# Yitran_IT900_Hutschiene_1_0.net
KiCad netlist of a schematic drawn in EAGLE
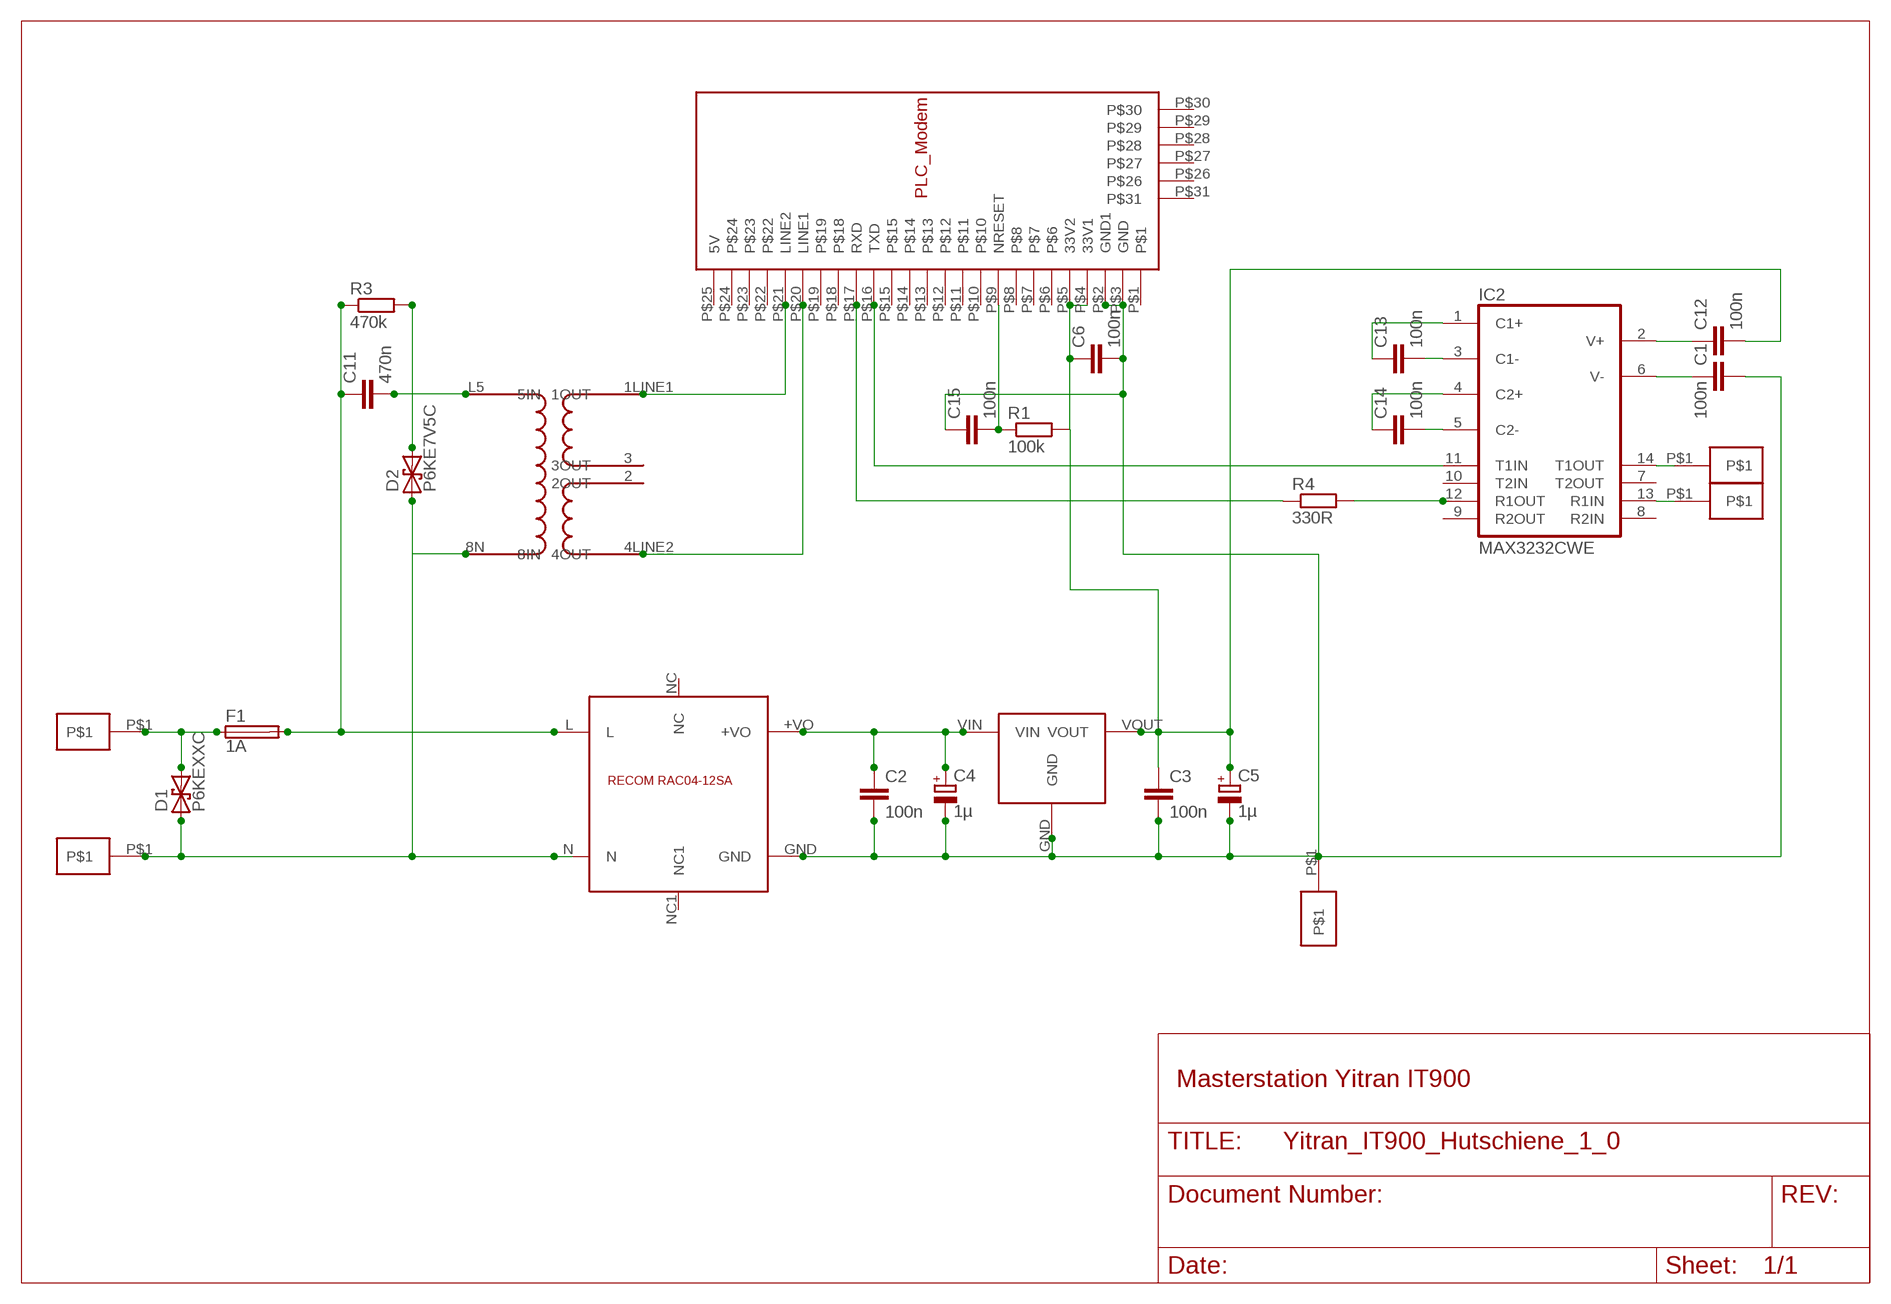
[diagram p0: schematic, sheet 1]

(export (version "E")
  (design (tool "Eeschema 10.0.6"))
  (components
    (comp (ref "C1")
      (value "100n")
      (footprint "eagle-import:C1206K")
      (libsource (lib "eagle-import") (part "C-EUC1206K"))
    )
    (comp (ref "C2")
      (value "100n")
      (footprint "eagle-import:C1206K")
      (libsource (lib "eagle-import") (part "C-EUC1206K"))
    )
    (comp (ref "C3")
      (value "100n")
      (footprint "eagle-import:C1206K")
      (libsource (lib "eagle-import") (part "C-EUC1206K"))
    )
    (comp (ref "C4")
      (value "1µ")
      (footprint "eagle-import:E2,5-5")
      (libsource (lib "eagle-import") (part "CPOL-EUE2.5-5"))
    )
    (comp (ref "C5")
      (value "1µ")
      (footprint "eagle-import:E2,5-5")
      (libsource (lib "eagle-import") (part "CPOL-EUE2.5-5"))
    )
    (comp (ref "C6")
      (value "100n")
      (footprint "eagle-import:C1206K")
      (libsource (lib "eagle-import") (part "C-EUC1206K"))
    )
    (comp (ref "C11")
      (value "470n")
      (footprint "eagle-import:C150-091X182")
      (libsource (lib "eagle-import") (part "C-EU150-091X182"))
    )
    (comp (ref "C12")
      (value "100n")
      (footprint "eagle-import:C1206K")
      (libsource (lib "eagle-import") (part "C-EUC1206K"))
    )
    (comp (ref "C13")
      (value "100n")
      (footprint "eagle-import:C1206K")
      (libsource (lib "eagle-import") (part "C-EUC1206K"))
    )
    (comp (ref "C14")
      (value "100n")
      (footprint "eagle-import:C1206K")
      (libsource (lib "eagle-import") (part "C-EUC1206K"))
    )
    (comp (ref "C15")
      (value "100n")
      (footprint "eagle-import:C1206K")
      (libsource (lib "eagle-import") (part "C-EUC1206K"))
    )
    (comp (ref "D1")
      (value "P6KEXXC")
      (footprint "eagle-import:CB417-15")
      (libsource (lib "eagle-import") (part "P6KEXXC"))
    )
    (comp (ref "D2")
      (value "P6KE7V5C")
      (footprint "eagle-import:CB417-15")
      (libsource (lib "eagle-import") (part "P6KEXXC"))
    )
    (comp (ref "F1")
      (value "1A")
      (footprint "eagle-import:TR5")
      (libsource (lib "eagle-import") (part "TR5"))
    )
    (comp (ref "GND")
      (value "PN4")
      (footprint "eagle-import:PIN2")
      (libsource (lib "eagle-import") (part "PN4"))
    )
    (comp (ref "IC2")
      (value "MAX3232CWE")
      (footprint "eagle-import:SO16L")
      (fields (field (name "MF") "MAXIM") (field (name "MPN") "MAX3232CWE+"))
      (libsource (lib "eagle-import") (part "MAX3232WEC"))
    )
    (comp (ref "PL1")
      (value "PN4")
      (footprint "eagle-import:PIN2")
      (libsource (lib "eagle-import") (part "PN4"))
    )
    (comp (ref "PL2")
      (value "PN4")
      (footprint "eagle-import:PIN2")
      (libsource (lib "eagle-import") (part "PN4"))
    )
    (comp (ref "R1")
      (value "100k")
      (footprint "eagle-import:M1406")
      (libsource (lib "eagle-import") (part "R-EU_M1406"))
    )
    (comp (ref "R3")
      (value "470k")
      (footprint "eagle-import:0309_10")
      (libsource (lib "eagle-import") (part "R-EU_0309/10"))
    )
    (comp (ref "R4")
      (value "330R")
      (footprint "eagle-import:R1206")
      (libsource (lib "eagle-import") (part "R-EU_R1206"))
    )
    (comp (ref "RXD")
      (value "PN4")
      (footprint "eagle-import:PIN2")
      (libsource (lib "eagle-import") (part "PN4"))
    )
    (comp (ref "TXD")
      (value "PN4")
      (footprint "eagle-import:PIN2")
      (libsource (lib "eagle-import") (part "PN4"))
    )
    (comp (ref "U$1")
      (value "RECOM_783_3")
      (footprint "eagle-import:RECOM785X")
      (libsource (lib "eagle-import") (part "RECOM_785_05"))
    )
    (comp (ref "U$3")
      (value "MODEMSTECKER")
      (footprint "eagle-import:MODEM_FUSS")
      (libsource (lib "eagle-import") (part "MODEMSTECKER"))
    )
    (comp (ref "U$9")
      (value "RECOM_RAC04_12SA")
      (footprint "eagle-import:RAC04_12SA")
      (libsource (lib "eagle-import") (part "RECOM_RAC04_12SA"))
    )
    (comp (ref "U$10")
      (value "PLC_UEBERTRAGER_V2")
      (footprint "eagle-import:PLC-UEBERTRAGER_V2")
      (libsource (lib "eagle-import") (part "PLC_UEBERTRAGER_V2"))
    )
  )
  (nets
    (net (code "1") (name "Net-(C2-Pad1)") (class "Default")
      (node (ref "C2") (pin "1") (pinfunction "1_1") (pintype "passive"))
      (node (ref "C4") (pin "+") (pinfunction "+_+") (pintype "passive"))
      (node (ref "U$1") (pin "VIN") (pinfunction "VIN_VIN") (pintype "bidirectional"))
      (node (ref "U$9") (pin "+VO") (pinfunction "+VO_+VO") (pintype "bidirectional"))
    )
    (net (code "2") (name "Net-(C11-Pad1)") (class "Default")
      (node (ref "C11") (pin "1") (pinfunction "1_1") (pintype "passive"))
      (node (ref "F1") (pin "2") (pinfunction "2_2") (pintype "passive"))
      (node (ref "R3") (pin "1") (pinfunction "1_1") (pintype "passive"))
      (node (ref "U$9") (pin "L") (pinfunction "L_L") (pintype "bidirectional"))
    )
    (net (code "3") (name "Net-(D1-1)") (class "Default")
      (node (ref "D1") (pin "A") (pinfunction "1_A") (pintype "passive"))
      (node (ref "D2") (pin "A") (pinfunction "1_A") (pintype "passive"))
      (node (ref "PL2") (pin "P$1") (pinfunction "P$1_P$1") (pintype "bidirectional"))
      (node (ref "U$10") (pin "8N") (pinfunction "8IN_8N") (pintype "input"))
      (node (ref "U$9") (pin "N") (pinfunction "N_N") (pintype "bidirectional"))
    )
    (net (code "4") (name "Net-(D1-2)") (class "Default")
      (node (ref "D1") (pin "C") (pinfunction "2_C") (pintype "passive"))
      (node (ref "F1") (pin "1") (pinfunction "1_1") (pintype "passive"))
      (node (ref "PL1") (pin "P$1") (pinfunction "P$1_P$1") (pintype "bidirectional"))
    )
    (net (code "5") (name "Net-(D2-2)") (class "Default")
      (node (ref "C11") (pin "2") (pinfunction "2_2") (pintype "passive"))
      (node (ref "D2") (pin "C") (pinfunction "2_C") (pintype "passive"))
      (node (ref "R3") (pin "2") (pinfunction "2_2") (pintype "passive"))
      (node (ref "U$10") (pin "L5") (pinfunction "5IN_L5") (pintype "input"))
    )
    (net (code "6") (name "Net-(IC2A-C1+)") (class "Default")
      (node (ref "C13") (pin "1") (pinfunction "1_1") (pintype "passive"))
      (node (ref "IC2") (pin "1") (pinfunction "C1+_1") (pintype "bidirectional"))
    )
    (net (code "7") (name "Net-(IC2A-C1-)") (class "Default")
      (node (ref "C13") (pin "2") (pinfunction "2_2") (pintype "passive"))
      (node (ref "IC2") (pin "3") (pinfunction "C1-_3") (pintype "bidirectional"))
    )
    (net (code "8") (name "Net-(IC2A-C2+)") (class "Default")
      (node (ref "C14") (pin "1") (pinfunction "1_1") (pintype "passive"))
      (node (ref "IC2") (pin "4") (pinfunction "C2+_4") (pintype "bidirectional"))
    )
    (net (code "9") (name "Net-(IC2A-C2-)") (class "Default")
      (node (ref "C14") (pin "2") (pinfunction "2_2") (pintype "passive"))
      (node (ref "IC2") (pin "5") (pinfunction "C2-_5") (pintype "bidirectional"))
    )
    (net (code "10") (name "Net-(IC2A-R1IN)") (class "Default")
      (node (ref "IC2") (pin "13") (pinfunction "R1IN_13") (pintype "input"))
      (node (ref "RXD") (pin "P$1") (pinfunction "P$1_P$1") (pintype "bidirectional"))
    )
    (net (code "11") (name "Net-(IC2A-R1OUT)") (class "Default")
      (node (ref "IC2") (pin "12") (pinfunction "R1OUT_12") (pintype "output"))
      (node (ref "R4") (pin "2") (pinfunction "2_2") (pintype "passive"))
    )
    (net (code "12") (name "Net-(IC2A-T1IN)") (class "Default")
      (node (ref "IC2") (pin "11") (pinfunction "T1IN_11") (pintype "input"))
      (node (ref "U$3") (pin "P$16") (pinfunction "TXD_P$16") (pintype "bidirectional"))
    )
    (net (code "13") (name "Net-(IC2A-T1OUT)") (class "Default")
      (node (ref "IC2") (pin "14") (pinfunction "T1OUT_14") (pintype "output"))
      (node (ref "TXD") (pin "P$1") (pinfunction "P$1_P$1") (pintype "bidirectional"))
    )
    (net (code "14") (name "Net-(IC2A-V+)") (class "Default")
      (node (ref "C12") (pin "1") (pinfunction "1_1") (pintype "passive"))
      (node (ref "IC2") (pin "2") (pinfunction "V+_2") (pintype "bidirectional"))
    )
    (net (code "15") (name "Net-(IC2A-V-)") (class "Default")
      (node (ref "C1") (pin "1") (pinfunction "1_1") (pintype "passive"))
      (node (ref "IC2") (pin "6") (pinfunction "V-_6") (pintype "bidirectional"))
    )
    (net (code "16") (name "Net-(U$3-33V1)") (class "Default")
      (node (ref "C12") (pin "2") (pinfunction "2_2") (pintype "passive"))
      (node (ref "C3") (pin "1") (pinfunction "1_1") (pintype "passive"))
      (node (ref "C5") (pin "+") (pinfunction "+_+") (pintype "passive"))
      (node (ref "C6") (pin "1") (pinfunction "1_1") (pintype "passive"))
      (node (ref "R1") (pin "2") (pinfunction "2_2") (pintype "passive"))
      (node (ref "U$1") (pin "VOUT") (pinfunction "VOUT_VOUT") (pintype "bidirectional"))
      (node (ref "U$3") (pin "P$4") (pinfunction "33V1_P$4") (pintype "bidirectional"))
      (node (ref "U$3") (pin "P$5") (pinfunction "33V2_P$5") (pintype "bidirectional"))
    )
    (net (code "17") (name "Net-(U$3-GND)") (class "Default")
      (node (ref "C1") (pin "2") (pinfunction "2_2") (pintype "passive"))
      (node (ref "C15") (pin "1") (pinfunction "1_1") (pintype "passive"))
      (node (ref "C2") (pin "2") (pinfunction "2_2") (pintype "passive"))
      (node (ref "C3") (pin "2") (pinfunction "2_2") (pintype "passive"))
      (node (ref "C4") (pin "-") (pinfunction "-_-") (pintype "passive"))
      (node (ref "C5") (pin "-") (pinfunction "-_-") (pintype "passive"))
      (node (ref "C6") (pin "2") (pinfunction "2_2") (pintype "passive"))
      (node (ref "GND") (pin "P$1") (pinfunction "P$1_P$1") (pintype "bidirectional"))
      (node (ref "U$1") (pin "GND") (pinfunction "GND_GND") (pintype "bidirectional"))
      (node (ref "U$3") (pin "P$2") (pinfunction "GND1_P$2") (pintype "bidirectional"))
      (node (ref "U$3") (pin "P$3") (pinfunction "GND_P$3") (pintype "bidirectional"))
      (node (ref "U$9") (pin "GND") (pinfunction "GND_GND") (pintype "bidirectional"))
    )
    (net (code "18") (name "Net-(U$3-NRESET)") (class "Default")
      (node (ref "C15") (pin "2") (pinfunction "2_2") (pintype "passive"))
      (node (ref "R1") (pin "1") (pinfunction "1_1") (pintype "passive"))
      (node (ref "U$3") (pin "P$9") (pinfunction "NRESET_P$9") (pintype "bidirectional"))
    )
    (net (code "19") (name "Net-(U$3-RXD)") (class "Default")
      (node (ref "R4") (pin "1") (pinfunction "1_1") (pintype "passive"))
      (node (ref "U$3") (pin "P$17") (pinfunction "RXD_P$17") (pintype "bidirectional"))
    )
    (net (code "20") (name "Net-(U$10-1OUT)") (class "Default")
      (node (ref "U$10") (pin "1LINE1") (pinfunction "1OUT_1LINE1") (pintype "output"))
      (node (ref "U$3") (pin "P$21") (pinfunction "LINE2_P$21") (pintype "bidirectional"))
    )
    (net (code "21") (name "Net-(U$10-4OUT)") (class "Default")
      (node (ref "U$10") (pin "4LINE2") (pinfunction "4OUT_4LINE2") (pintype "output"))
      (node (ref "U$3") (pin "P$20") (pinfunction "LINE1_P$20") (pintype "bidirectional"))
    )
    (net (code "22") (name "unconnected-(IC2A-R2IN-Pad8)") (class "Default")
      (node (ref "IC2") (pin "8") (pinfunction "R2IN_8") (pintype "input"))
    )
    (net (code "23") (name "unconnected-(IC2A-R2OUT-Pad9)") (class "Default")
      (node (ref "IC2") (pin "9") (pinfunction "R2OUT_9") (pintype "output"))
    )
    (net (code "24") (name "unconnected-(IC2A-T2IN-Pad10)") (class "Default")
      (node (ref "IC2") (pin "10") (pinfunction "T2IN_10") (pintype "input"))
    )
    (net (code "25") (name "unconnected-(IC2A-T2OUT-Pad7)") (class "Default")
      (node (ref "IC2") (pin "7") (pinfunction "T2OUT_7") (pintype "output"))
    )
    (net (code "26") (name "unconnected-(U$3-5V-PadP$25)") (class "Default")
      (node (ref "U$3") (pin "P$25") (pinfunction "5V_P$25") (pintype "bidirectional"))
    )
    (net (code "27") (name "unconnected-(U$3-PadP$1)") (class "Default")
      (node (ref "U$3") (pin "P$1") (pinfunction "P$1_P$1") (pintype "bidirectional"))
    )
    (net (code "28") (name "unconnected-(U$3-PadP$6)") (class "Default")
      (node (ref "U$3") (pin "P$6") (pinfunction "P$6_P$6") (pintype "bidirectional"))
    )
    (net (code "29") (name "unconnected-(U$3-PadP$7)") (class "Default")
      (node (ref "U$3") (pin "P$7") (pinfunction "P$7_P$7") (pintype "bidirectional"))
    )
    (net (code "30") (name "unconnected-(U$3-PadP$8)") (class "Default")
      (node (ref "U$3") (pin "P$8") (pinfunction "P$8_P$8") (pintype "bidirectional"))
    )
    (net (code "31") (name "unconnected-(U$3-PadP$10)") (class "Default")
      (node (ref "U$3") (pin "P$10") (pinfunction "P$10_P$10") (pintype "bidirectional"))
    )
    (net (code "32") (name "unconnected-(U$3-PadP$11)") (class "Default")
      (node (ref "U$3") (pin "P$11") (pinfunction "P$11_P$11") (pintype "bidirectional"))
    )
    (net (code "33") (name "unconnected-(U$3-PadP$12)") (class "Default")
      (node (ref "U$3") (pin "P$12") (pinfunction "P$12_P$12") (pintype "bidirectional"))
    )
    (net (code "34") (name "unconnected-(U$3-PadP$13)") (class "Default")
      (node (ref "U$3") (pin "P$13") (pinfunction "P$13_P$13") (pintype "bidirectional"))
    )
    (net (code "35") (name "unconnected-(U$3-PadP$14)") (class "Default")
      (node (ref "U$3") (pin "P$14") (pinfunction "P$14_P$14") (pintype "bidirectional"))
    )
    (net (code "36") (name "unconnected-(U$3-PadP$15)") (class "Default")
      (node (ref "U$3") (pin "P$15") (pinfunction "P$15_P$15") (pintype "bidirectional"))
    )
    (net (code "37") (name "unconnected-(U$3-PadP$18)") (class "Default")
      (node (ref "U$3") (pin "P$18") (pinfunction "P$18_P$18") (pintype "bidirectional"))
    )
    (net (code "38") (name "unconnected-(U$3-PadP$19)") (class "Default")
      (node (ref "U$3") (pin "P$19") (pinfunction "P$19_P$19") (pintype "bidirectional"))
    )
    (net (code "39") (name "unconnected-(U$3-PadP$22)") (class "Default")
      (node (ref "U$3") (pin "P$22") (pinfunction "P$22_P$22") (pintype "bidirectional"))
    )
    (net (code "40") (name "unconnected-(U$3-PadP$23)") (class "Default")
      (node (ref "U$3") (pin "P$23") (pinfunction "P$23_P$23") (pintype "bidirectional"))
    )
    (net (code "41") (name "unconnected-(U$3-PadP$24)") (class "Default")
      (node (ref "U$3") (pin "P$24") (pinfunction "P$24_P$24") (pintype "bidirectional"))
    )
    (net (code "42") (name "unconnected-(U$3-PadP$26)") (class "Default")
      (node (ref "U$3") (pin "P$26") (pinfunction "P$26_P$26") (pintype "bidirectional"))
    )
    (net (code "43") (name "unconnected-(U$3-PadP$27)") (class "Default")
      (node (ref "U$3") (pin "P$27") (pinfunction "P$27_P$27") (pintype "bidirectional"))
    )
    (net (code "44") (name "unconnected-(U$3-PadP$28)") (class "Default")
      (node (ref "U$3") (pin "P$28") (pinfunction "P$28_P$28") (pintype "bidirectional"))
    )
    (net (code "45") (name "unconnected-(U$3-PadP$29)") (class "Default")
      (node (ref "U$3") (pin "P$29") (pinfunction "P$29_P$29") (pintype "bidirectional"))
    )
    (net (code "46") (name "unconnected-(U$3-PadP$30)") (class "Default")
      (node (ref "U$3") (pin "P$30") (pinfunction "P$30_P$30") (pintype "bidirectional"))
    )
    (net (code "47") (name "unconnected-(U$3-PadP$31)") (class "Default")
      (node (ref "U$3") (pin "P$31") (pinfunction "P$31_P$31") (pintype "bidirectional"))
    )
    (net (code "48") (name "unconnected-(U$9-PadNC)") (class "Default")
      (node (ref "U$9") (pin "NC") (pinfunction "NC_NC") (pintype "bidirectional"))
    )
    (net (code "49") (name "unconnected-(U$9-PadNC1)") (class "Default")
      (node (ref "U$9") (pin "NC1") (pinfunction "NC1_NC1") (pintype "bidirectional"))
    )
    (net (code "50") (name "unconnected-(U$10-2OUT-Pad2)") (class "Default")
      (node (ref "U$10") (pin "2") (pinfunction "2OUT_2") (pintype "output"))
    )
    (net (code "51") (name "unconnected-(U$10-3OUT-Pad3)") (class "Default")
      (node (ref "U$10") (pin "3") (pinfunction "3OUT_3") (pintype "output"))
    )
  )
)
